# PLWD_GNSS_RF.net
KiCad netlist of a schematic drawn in Altium Designer
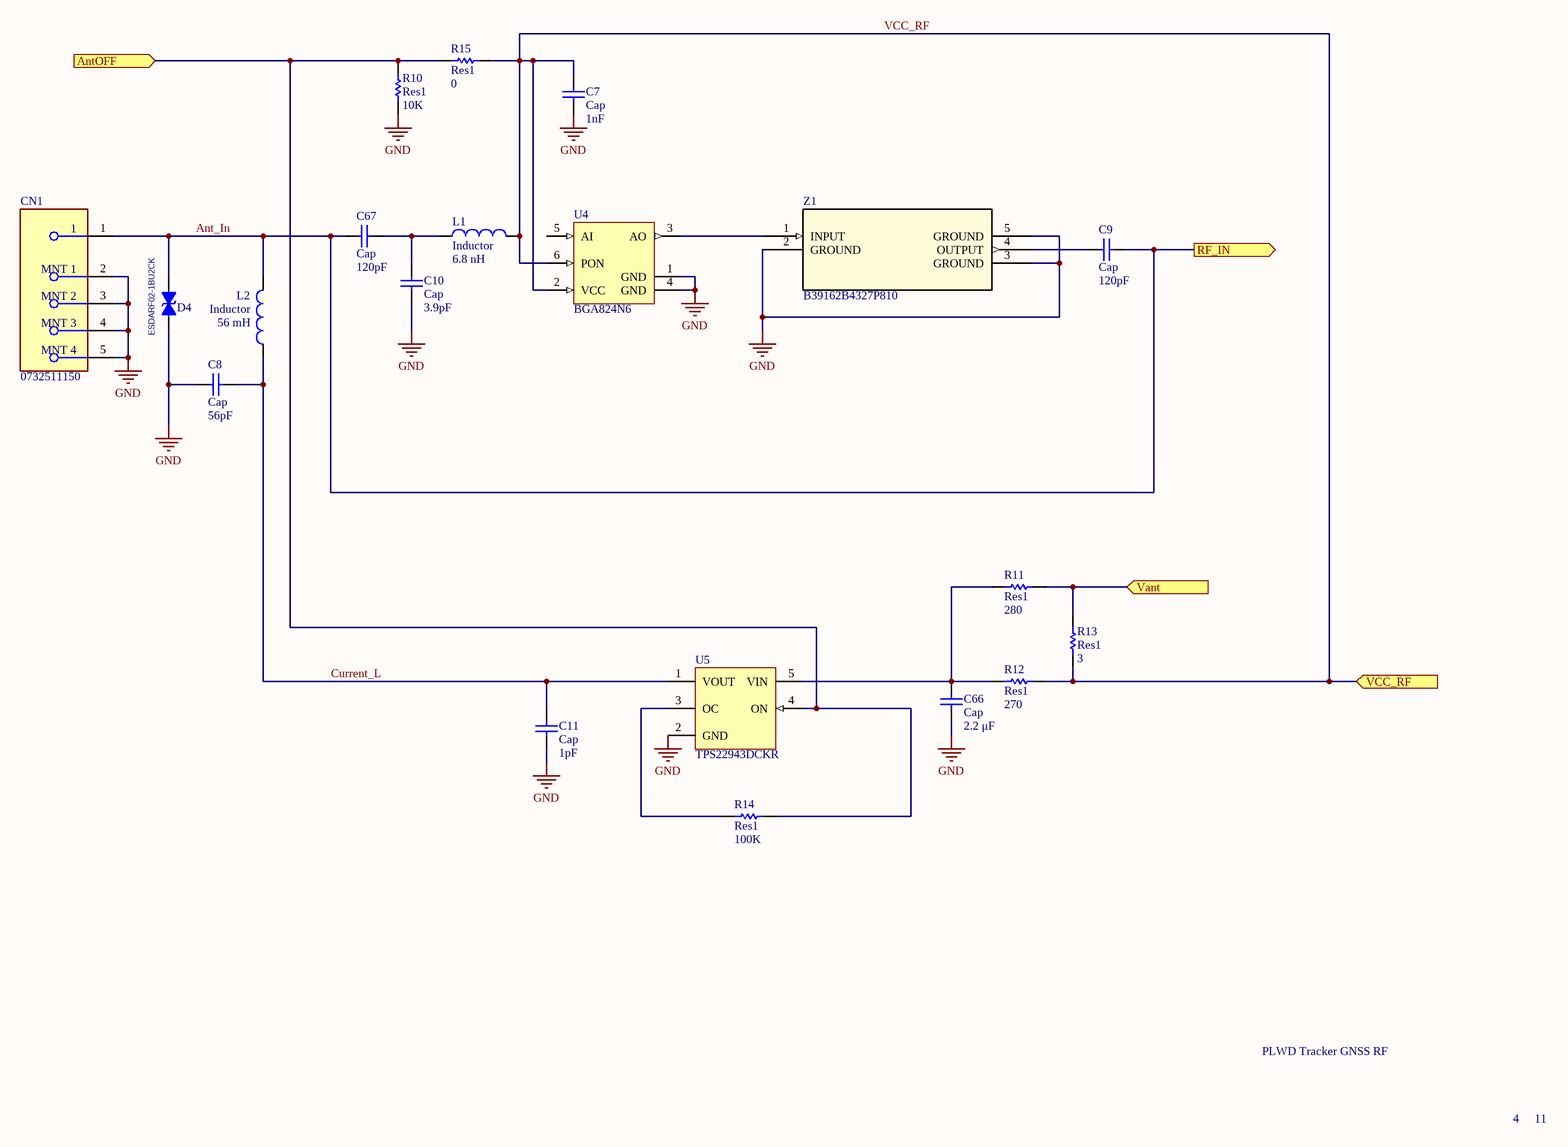
[diagram p0: PLWD_GNSS_RF.SchDoc]

(export (version "E")
  (design (tool "Eeschema 10.0.6"))
  (components
    (comp (ref "C7")
      (value "Cap")
      (footprint "RAD-0.3")
      (description "Capacitor")
      (fields (field (name "ALTIUM_VALUE") "1nF") (field (name "PUBLISHER") "Altium Limited"))
      (libsource (lib "Miscellaneous Devices") (part "Cap"))
    )
    (comp (ref "C8")
      (value "Cap")
      (footprint "RAD-0.3")
      (description "Capacitor")
      (fields (field (name "ALTIUM_VALUE") "56pF") (field (name "PUBLISHER") "Altium Limited"))
      (libsource (lib "Miscellaneous Devices") (part "Cap"))
    )
    (comp (ref "C9")
      (value "Cap")
      (footprint "RAD-0.3")
      (description "Capacitor")
      (fields (field (name "ALTIUM_VALUE") "120pF") (field (name "PUBLISHER") "Altium Limited"))
      (libsource (lib "Miscellaneous Devices") (part "Cap"))
    )
    (comp (ref "C10")
      (value "Cap")
      (footprint "RAD-0.3")
      (description "Capacitor")
      (fields (field (name "ALTIUM_VALUE") "3.9pF") (field (name "PUBLISHER") "Altium Limited"))
      (libsource (lib "Miscellaneous Devices") (part "Cap"))
    )
    (comp (ref "C11")
      (value "Cap")
      (footprint "RAD-0.3")
      (description "Capacitor")
      (fields (field (name "ALTIUM_VALUE") "1pF") (field (name "PUBLISHER") "Altium Limited"))
      (libsource (lib "Miscellaneous Devices") (part "Cap"))
    )
    (comp (ref "C66")
      (value "Cap")
      (footprint "RAD-0.3")
      (description "Capacitor")
      (fields (field (name "ALTIUM_VALUE") "2.2 μF") (field (name "PUBLISHER") "Altium Limited"))
      (libsource (lib "Miscellaneous Devices") (part "Cap"))
    )
    (comp (ref "C67")
      (value "Cap")
      (footprint "RAD-0.3")
      (description "Capacitor")
      (fields (field (name "ALTIUM_VALUE") "120pF") (field (name "PUBLISHER") "Altium Limited"))
      (libsource (lib "Miscellaneous Devices") (part "Cap"))
    )
    (comp (ref "CN1")
      (value "0732511150")
      (footprint "FP-0732511150-MFG")
      (description "CONN SMA RCPT STR 50OHM EDGE MNT")
      (fields
        (field (name "MANUFACTURER") "Molex Inc")
        (field (name "OCTOPART") "https://octopart.com/73251-1150-molex-777272")
      )
      (libsource (lib "Altium Content Vault") (part "2361b00c12d1e236ec859c20ad68b22"))
    )
    (comp (ref "D4")
      (value "ESDARF02-1BU2CK")
      (footprint "ST_0201B")
      (libsource (lib "ESDARF02-1BU2CK") (part "ESDARF02-1BU2CK"))
    )
    (comp (ref "L1")
      (value "Inductor")
      (footprint "0402-A")
      (fields (field (name "ALTIUM_VALUE") "6.8 nH") (field (name "PUBLISHER") "Altium Limited"))
      (libsource (lib "Miscellaneous Devices") (part "Inductor"))
    )
    (comp (ref "L2")
      (value "Inductor")
      (footprint "0402-A")
      (fields (field (name "ALTIUM_VALUE") "56 mH") (field (name "PUBLISHER") "Altium Limited"))
      (libsource (lib "Miscellaneous Devices") (part "Inductor"))
    )
    (comp (ref "R10")
      (value "Res1")
      (footprint "AXIAL-0.3")
      (description "Resistor")
      (fields (field (name "ALTIUM_VALUE") "10K") (field (name "PUBLISHER") "Altium Limited"))
      (libsource (lib "Miscellaneous Devices") (part "Res1"))
    )
    (comp (ref "R11")
      (value "Res1")
      (footprint "AXIAL-0.3")
      (description "Resistor")
      (fields (field (name "ALTIUM_VALUE") "280") (field (name "PUBLISHER") "Altium Limited"))
      (libsource (lib "Miscellaneous Devices") (part "Res1"))
    )
    (comp (ref "R12")
      (value "Res1")
      (footprint "AXIAL-0.3")
      (description "Resistor")
      (fields (field (name "ALTIUM_VALUE") "270") (field (name "PUBLISHER") "Altium Limited"))
      (libsource (lib "Miscellaneous Devices") (part "Res1"))
    )
    (comp (ref "R13")
      (value "Res1")
      (footprint "AXIAL-0.3")
      (description "Resistor")
      (fields (field (name "ALTIUM_VALUE") "3") (field (name "PUBLISHER") "Altium Limited"))
      (libsource (lib "Miscellaneous Devices") (part "Res1"))
    )
    (comp (ref "R14")
      (value "Res1")
      (footprint "AXIAL-0.3")
      (description "Resistor")
      (fields (field (name "ALTIUM_VALUE") "100K") (field (name "PUBLISHER") "Altium Limited"))
      (libsource (lib "Miscellaneous Devices") (part "Res1"))
    )
    (comp (ref "R15")
      (value "Res1")
      (footprint "AXIAL-0.3")
      (description "Resistor")
      (fields (field (name "ALTIUM_VALUE") "0") (field (name "PUBLISHER") "Altium Limited"))
      (libsource (lib "Miscellaneous Devices") (part "Res1"))
    )
    (comp (ref "U4")
      (value "BGA824N6")
      (footprint "INF-TSNP-6-2_V")
      (fields (field (name "MANUFACTURER") "Infineon"))
      (libsource (lib "Altium Content Vault") (part "INF-BGAXXXN6_E6327-TSNP-6-2-6"))
    )
    (comp (ref "U5")
      (value "TPS22943DCKR")
      (footprint "DCK0005A_N")
      (fields (field (name "MANUFACTURER") "Texas Instruments"))
      (libsource (lib "Altium Content Vault") (part "TI-TPS22943DCK5"))
    )
    (comp (ref "Z1")
      (value "B39162B4327P810")
      (footprint "B39162B4327P810_TDK")
      (description "No Description Available")
      (fields (field (name "COPYRIGHT") "Copyright (C) 2022 Ultra Librarian. All rights reserved."))
      (libsource (lib "B39162B4327P810") (part "B39162B4327P810"))
    )
  )
  (nets
    (net (code "1") (name "/AntOFF") (class "Default")
      (node (ref "R10") (pin "2") (pinfunction "2_2") (pintype "passive"))
      (node (ref "R14") (pin "2") (pinfunction "2_2") (pintype "passive"))
      (node (ref "R15") (pin "1") (pinfunction "1_1") (pintype "passive"))
      (node (ref "U5") (pin "4") (pinfunction "ON_4") (pintype "input"))
    )
    (net (code "2") (name "/Ant_In") (class "Default")
      (node (ref "C67") (pin "1") (pinfunction "1_1") (pintype "passive"))
      (node (ref "C9") (pin "2") (pinfunction "2_2") (pintype "passive"))
      (node (ref "CN1") (pin "1") (pinfunction "1_1") (pintype "passive"))
      (node (ref "D4") (pin "2") (pinfunction "2_2") (pintype "passive"))
      (node (ref "L2") (pin "2") (pinfunction "2_2") (pintype "passive"))
    )
    (net (code "3") (name "/Current_L") (class "Default")
      (node (ref "C11") (pin "2") (pinfunction "2_2") (pintype "passive"))
      (node (ref "C8") (pin "2") (pinfunction "2_2") (pintype "passive"))
      (node (ref "L2") (pin "1") (pinfunction "1_1") (pintype "passive"))
      (node (ref "U5") (pin "1") (pinfunction "VOUT_1") (pintype "power_in"))
    )
    (net (code "4") (name "/VCC_RF") (class "Default")
      (node (ref "C7") (pin "2") (pinfunction "2_2") (pintype "passive"))
      (node (ref "L1") (pin "2") (pinfunction "2_2") (pintype "passive"))
      (node (ref "R12") (pin "2") (pinfunction "2_2") (pintype "passive"))
      (node (ref "R13") (pin "1") (pinfunction "1_1") (pintype "passive"))
      (node (ref "R15") (pin "2") (pinfunction "2_2") (pintype "passive"))
      (node (ref "U4") (pin "2") (pinfunction "VCC_2") (pintype "input"))
      (node (ref "U4") (pin "6") (pinfunction "PON_6") (pintype "input"))
    )
    (net (code "5") (name "/Vant") (class "Default")
      (node (ref "R11") (pin "2") (pinfunction "2_2") (pintype "passive"))
      (node (ref "R13") (pin "2") (pinfunction "2_2") (pintype "passive"))
    )
    (net (code "6") (name "GND") (class "Default")
      (node (ref "C10") (pin "1") (pinfunction "1_1") (pintype "passive"))
      (node (ref "C11") (pin "1") (pinfunction "1_1") (pintype "passive"))
      (node (ref "C66") (pin "1") (pinfunction "1_1") (pintype "passive"))
      (node (ref "C7") (pin "1") (pinfunction "1_1") (pintype "passive"))
      (node (ref "C8") (pin "1") (pinfunction "1_1") (pintype "passive"))
      (node (ref "CN1") (pin "2") (pinfunction "MNT_1_2") (pintype "passive"))
      (node (ref "CN1") (pin "3") (pinfunction "MNT_2_3") (pintype "passive"))
      (node (ref "CN1") (pin "4") (pinfunction "MNT_3_4") (pintype "passive"))
      (node (ref "CN1") (pin "5") (pinfunction "MNT_4_5") (pintype "passive"))
      (node (ref "D4") (pin "1") (pinfunction "1_1") (pintype "passive"))
      (node (ref "R10") (pin "1") (pinfunction "1_1") (pintype "passive"))
      (node (ref "U4") (pin "1") (pinfunction "GND_1") (pintype "power_in"))
      (node (ref "U4") (pin "4") (pinfunction "GND_4") (pintype "power_in"))
      (node (ref "U5") (pin "2") (pinfunction "GND_2") (pintype "power_in"))
      (node (ref "Z1") (pin "2") (pinfunction "GROUND_2") (pintype "passive"))
      (node (ref "Z1") (pin "3") (pinfunction "GROUND_3") (pintype "passive"))
      (node (ref "Z1") (pin "5") (pinfunction "GROUND_5") (pintype "passive"))
    )
    (net (code "7") (name "Net-(C10-Pad2)") (class "Default")
      (node (ref "C10") (pin "2") (pinfunction "2_2") (pintype "passive"))
      (node (ref "C67") (pin "2") (pinfunction "2_2") (pintype "passive"))
      (node (ref "L1") (pin "1") (pinfunction "1_1") (pintype "passive"))
    )
    (net (code "8") (name "Net-(U4-AO)") (class "Default")
      (node (ref "U4") (pin "3") (pinfunction "AO_3") (pintype "output"))
      (node (ref "Z1") (pin "1") (pinfunction "INPUT_1") (pintype "input"))
    )
    (net (code "9") (name "Net-(U5-OC)") (class "Default")
      (node (ref "R14") (pin "1") (pinfunction "1_1") (pintype "passive"))
      (node (ref "U5") (pin "3") (pinfunction "OC_3") (pintype "open_collector"))
    )
    (net (code "10") (name "Net-(U5-VIN)") (class "Default")
      (node (ref "C66") (pin "2") (pinfunction "2_2") (pintype "passive"))
      (node (ref "R11") (pin "1") (pinfunction "1_1") (pintype "passive"))
      (node (ref "R12") (pin "1") (pinfunction "1_1") (pintype "passive"))
      (node (ref "U5") (pin "5") (pinfunction "VIN_5") (pintype "power_in"))
    )
    (net (code "11") (name "Net-(Z1-OUTPUT)") (class "Default")
      (node (ref "C9") (pin "1") (pinfunction "1_1") (pintype "passive"))
      (node (ref "Z1") (pin "4") (pinfunction "OUTPUT_4") (pintype "output"))
    )
    (net (code "12") (name "unconnected-(U4-AI-Pad5)") (class "Default")
      (node (ref "U4") (pin "5") (pinfunction "AI_5") (pintype "input"))
    )
  )
)
